# 03_-_mPCIe_Connector.net
KiCad netlist of a schematic drawn in Altium Designer
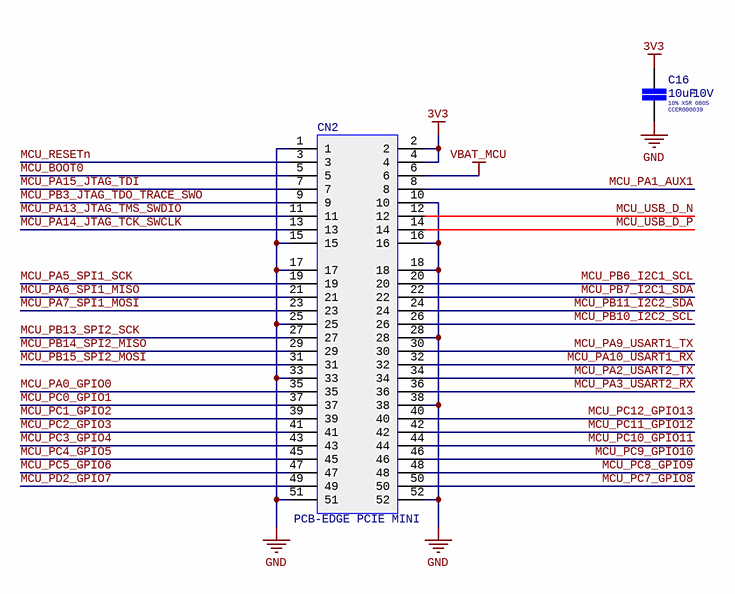
[diagram p0: [03] - mPCIe Connector.SchDoc]

(export (version "E")
  (design (tool "Eeschema 10.0.6"))
  (components
    (comp (ref "C16")
      (value "10uF 10V")
      (footprint "CAP-SMD-0805-1.35MM-IPC-MED")
      (description "CAP CER 10U 10V X5R 10% SMD 0805 85C SAMSUNG")
      (fields
        (field (name "VOLTAGE") "10V")
        (field (name "INTERNAL PART NUMBER") "CCER000039")
        (field (name "TOLERANCE") "10%")
        (field (name "VOLTAGE RATING") "10V")
        (field (name "DIELECTRIC") "X5R")
        (field (name "CASE/PACKAGE") "0805")
        (field (name "CAPACITANCE") "10uF")
      )
      (libsource (lib "Altium_Lib_Standard") (part "CL21A106KPFNNNG"))
    )
    (comp (ref "CN2")
      (value "PCB-EDGE PCIE MINI")
      (footprint "CON-PCB-EDGE-PCIE-MINI-CARD-52POS")
      (description "PCIE MINI CARD PCB EDGE")
      (libsource (lib "Altium_Lib_Standard") (part "PCB-EDGE PCIE MINI"))
    )
  )
  (nets
    (net (code "1") (name "/MCU_BOOT0") (class "Default")
      (node (ref "CN2") (pin "5") (pinfunction "5_5") (pintype "passive"))
    )
    (net (code "2") (name "/MCU_PA0_GPIO0") (class "Default")
      (node (ref "CN2") (pin "35") (pinfunction "35_35") (pintype "passive"))
    )
    (net (code "3") (name "/MCU_PA1_AUX1") (class "Default")
      (node (ref "CN2") (pin "8") (pinfunction "8_8") (pintype "passive"))
    )
    (net (code "4") (name "/MCU_PA2_USART2_TX") (class "Default")
      (node (ref "CN2") (pin "34") (pinfunction "34_34") (pintype "passive"))
    )
    (net (code "5") (name "/MCU_PA3_USART2_RX") (class "Default")
      (node (ref "CN2") (pin "36") (pinfunction "36_36") (pintype "passive"))
    )
    (net (code "6") (name "/MCU_PA5_SPI1_SCK") (class "Default")
      (node (ref "CN2") (pin "19") (pinfunction "19_19") (pintype "passive"))
    )
    (net (code "7") (name "/MCU_PA6_SPI1_MISO") (class "Default")
      (node (ref "CN2") (pin "21") (pinfunction "21_21") (pintype "passive"))
    )
    (net (code "8") (name "/MCU_PA7_SPI1_MOSI") (class "Default")
      (node (ref "CN2") (pin "23") (pinfunction "23_23") (pintype "passive"))
    )
    (net (code "9") (name "/MCU_PA9_USART1_TX") (class "Default")
      (node (ref "CN2") (pin "30") (pinfunction "30_30") (pintype "passive"))
    )
    (net (code "10") (name "/MCU_PA10_USART1_RX") (class "Default")
      (node (ref "CN2") (pin "32") (pinfunction "32_32") (pintype "passive"))
    )
    (net (code "11") (name "/MCU_PA13_JTAG_TMS_SWDIO") (class "Default")
      (node (ref "CN2") (pin "11") (pinfunction "11_11") (pintype "passive"))
    )
    (net (code "12") (name "/MCU_PA14_JTAG_TCK_SWCLK") (class "Default")
      (node (ref "CN2") (pin "13") (pinfunction "13_13") (pintype "passive"))
    )
    (net (code "13") (name "/MCU_PA15_JTAG_TDI") (class "Default")
      (node (ref "CN2") (pin "7") (pinfunction "7_7") (pintype "passive"))
    )
    (net (code "14") (name "/MCU_PB3_JTAG_TDO_TRACE_SWO") (class "Default")
      (node (ref "CN2") (pin "9") (pinfunction "9_9") (pintype "passive"))
    )
    (net (code "15") (name "/MCU_PB6_I2C1_SCL") (class "Default")
      (node (ref "CN2") (pin "20") (pinfunction "20_20") (pintype "passive"))
    )
    (net (code "16") (name "/MCU_PB7_I2C1_SDA") (class "Default")
      (node (ref "CN2") (pin "22") (pinfunction "22_22") (pintype "passive"))
    )
    (net (code "17") (name "/MCU_PB10_I2C2_SCL") (class "Default")
      (node (ref "CN2") (pin "26") (pinfunction "26_26") (pintype "passive"))
    )
    (net (code "18") (name "/MCU_PB11_I2C2_SDA") (class "Default")
      (node (ref "CN2") (pin "24") (pinfunction "24_24") (pintype "passive"))
    )
    (net (code "19") (name "/MCU_PB13_SPI2_SCK") (class "Default")
      (node (ref "CN2") (pin "27") (pinfunction "27_27") (pintype "passive"))
    )
    (net (code "20") (name "/MCU_PB14_SPI2_MISO") (class "Default")
      (node (ref "CN2") (pin "29") (pinfunction "29_29") (pintype "passive"))
    )
    (net (code "21") (name "/MCU_PB15_SPI2_MOSI") (class "Default")
      (node (ref "CN2") (pin "31") (pinfunction "31_31") (pintype "passive"))
    )
    (net (code "22") (name "/MCU_PC0_GPIO1") (class "Default")
      (node (ref "CN2") (pin "37") (pinfunction "37_37") (pintype "passive"))
    )
    (net (code "23") (name "/MCU_PC1_GPIO2") (class "Default")
      (node (ref "CN2") (pin "39") (pinfunction "39_39") (pintype "passive"))
    )
    (net (code "24") (name "/MCU_PC2_GPIO3") (class "Default")
      (node (ref "CN2") (pin "41") (pinfunction "41_41") (pintype "passive"))
    )
    (net (code "25") (name "/MCU_PC3_GPIO4") (class "Default")
      (node (ref "CN2") (pin "43") (pinfunction "43_43") (pintype "passive"))
    )
    (net (code "26") (name "/MCU_PC4_GPIO5") (class "Default")
      (node (ref "CN2") (pin "45") (pinfunction "45_45") (pintype "passive"))
    )
    (net (code "27") (name "/MCU_PC5_GPIO6") (class "Default")
      (node (ref "CN2") (pin "47") (pinfunction "47_47") (pintype "passive"))
    )
    (net (code "28") (name "/MCU_PC7_GPIO8") (class "Default")
      (node (ref "CN2") (pin "50") (pinfunction "50_50") (pintype "passive"))
    )
    (net (code "29") (name "/MCU_PC8_GPIO9") (class "Default")
      (node (ref "CN2") (pin "48") (pinfunction "48_48") (pintype "passive"))
    )
    (net (code "30") (name "/MCU_PC9_GPIO10") (class "Default")
      (node (ref "CN2") (pin "46") (pinfunction "46_46") (pintype "passive"))
    )
    (net (code "31") (name "/MCU_PC10_GPIO11") (class "Default")
      (node (ref "CN2") (pin "44") (pinfunction "44_44") (pintype "passive"))
    )
    (net (code "32") (name "/MCU_PC11_GPIO12") (class "Default")
      (node (ref "CN2") (pin "42") (pinfunction "42_42") (pintype "passive"))
    )
    (net (code "33") (name "/MCU_PC12_GPIO13") (class "Default")
      (node (ref "CN2") (pin "40") (pinfunction "40_40") (pintype "passive"))
    )
    (net (code "34") (name "/MCU_PD2_GPIO7") (class "Default")
      (node (ref "CN2") (pin "49") (pinfunction "49_49") (pintype "passive"))
    )
    (net (code "35") (name "/MCU_RESETn") (class "Default")
      (node (ref "CN2") (pin "3") (pinfunction "3_3") (pintype "passive"))
    )
    (net (code "36") (name "/MCU_USB_D_N") (class "Default")
      (node (ref "CN2") (pin "12") (pinfunction "12_12") (pintype "passive"))
    )
    (net (code "37") (name "/MCU_USB_D_P") (class "Default")
      (node (ref "CN2") (pin "14") (pinfunction "14_14") (pintype "passive"))
    )
    (net (code "38") (name "3V3") (class "Default")
      (node (ref "C16") (pin "1") (pinfunction "1_1") (pintype "passive"))
      (node (ref "CN2") (pin "2") (pinfunction "2_2") (pintype "passive"))
      (node (ref "CN2") (pin "4") (pinfunction "4_4") (pintype "passive"))
    )
    (net (code "39") (name "GND") (class "Default")
      (node (ref "C16") (pin "2") (pinfunction "2_2") (pintype "passive"))
      (node (ref "CN2") (pin "1") (pinfunction "1_1") (pintype "passive"))
      (node (ref "CN2") (pin "10") (pinfunction "10_10") (pintype "passive"))
      (node (ref "CN2") (pin "15") (pinfunction "15_15") (pintype "passive"))
      (node (ref "CN2") (pin "16") (pinfunction "16_16") (pintype "passive"))
      (node (ref "CN2") (pin "17") (pinfunction "17_17") (pintype "passive"))
      (node (ref "CN2") (pin "18") (pinfunction "18_18") (pintype "passive"))
      (node (ref "CN2") (pin "25") (pinfunction "25_25") (pintype "passive"))
      (node (ref "CN2") (pin "28") (pinfunction "28_28") (pintype "passive"))
      (node (ref "CN2") (pin "33") (pinfunction "33_33") (pintype "passive"))
      (node (ref "CN2") (pin "38") (pinfunction "38_38") (pintype "passive"))
      (node (ref "CN2") (pin "51") (pinfunction "51_51") (pintype "passive"))
      (node (ref "CN2") (pin "52") (pinfunction "52_52") (pintype "passive"))
    )
    (net (code "40") (name "VBAT_MCU") (class "Default")
      (node (ref "CN2") (pin "6") (pinfunction "6_6") (pintype "passive"))
    )
  )
)
